# FLASH.net
KiCad netlist of a schematic drawn in Altium Designer
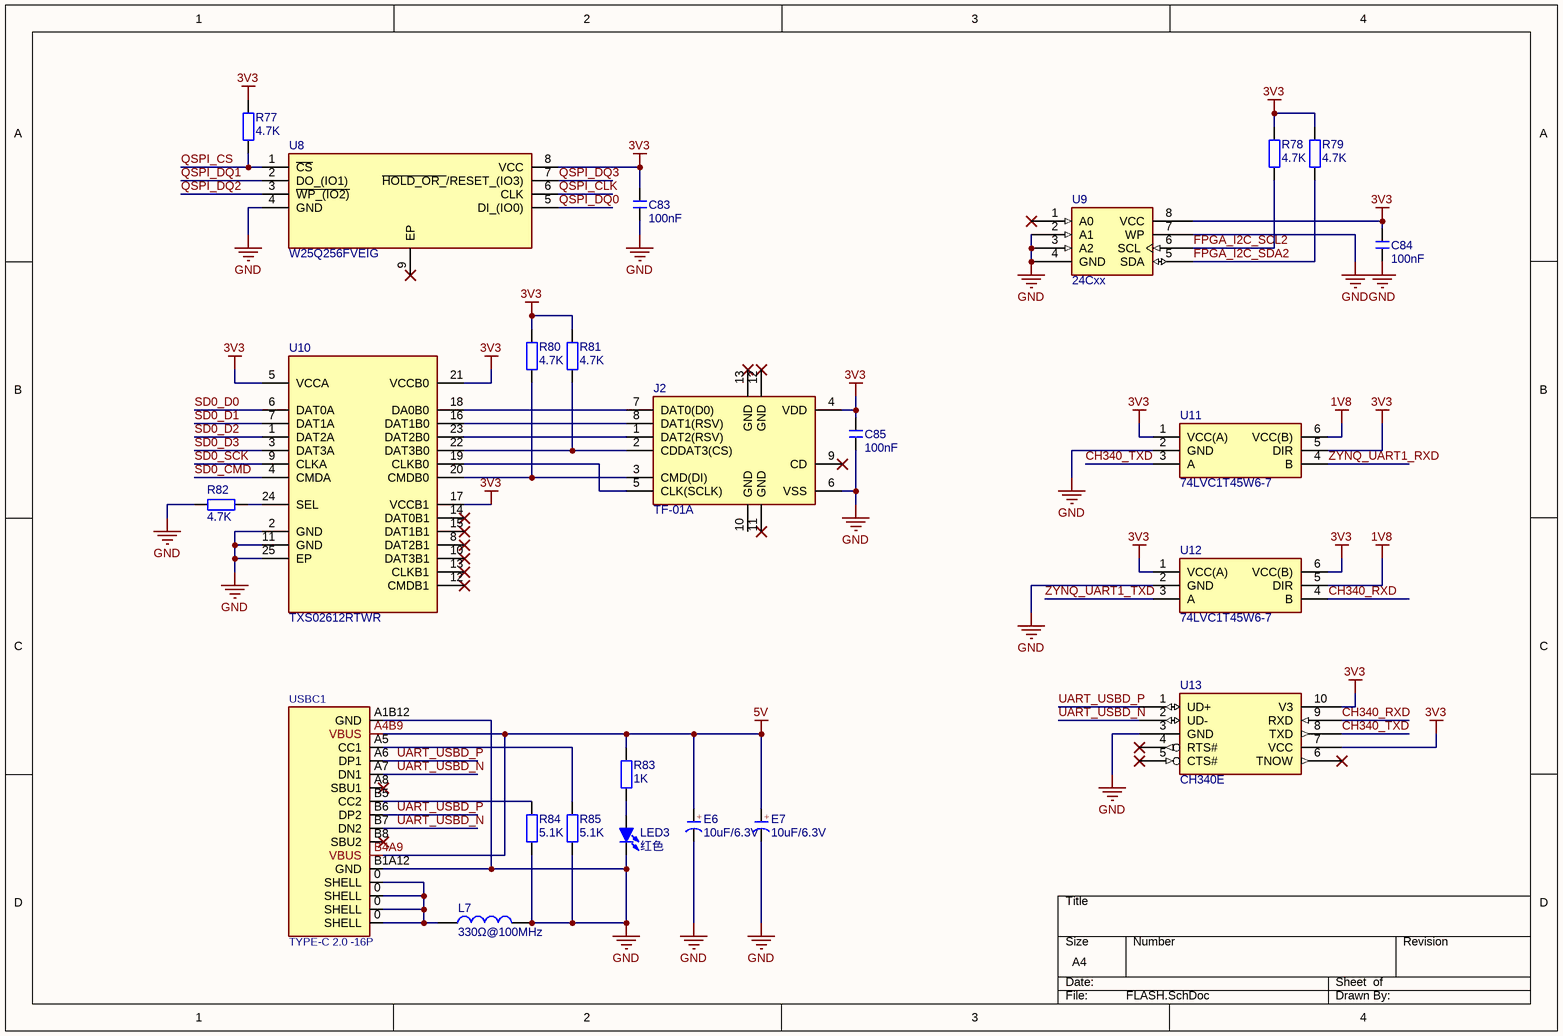
[diagram p0: FLASH.SchDoc]

(export (version "E")
  (design (tool "Eeschema 10.0.6"))
  (components
    (comp (ref "C83")
      (value "100nF")
      (footprint "C 0402_L")
      (description "无极性贴片电容")
      (fields (field (name "版权归属") "源创客"))
      (libsource (lib "3.1   - 电阻-电容-电感") (part "C"))
    )
    (comp (ref "C84")
      (value "100nF")
      (footprint "C 0402_L")
      (description "无极性贴片电容")
      (fields (field (name "版权归属") "源创客"))
      (libsource (lib "3.1   - 电阻-电容-电感") (part "C"))
    )
    (comp (ref "C85")
      (value "100nF")
      (footprint "C 0402_L")
      (description "无极性贴片电容")
      (fields (field (name "版权归属") "源创客"))
      (libsource (lib "3.1   - 电阻-电容-电感") (part "C"))
    )
    (comp (ref "E6")
      (value "10uF/6.3V")
      (footprint "CD A(3216)")
      (description "贴片钽电容")
      (fields (field (name "版权归属") "源创客"))
      (libsource (lib "3.1   - 电阻-电容-电感") (part "C-CD"))
    )
    (comp (ref "E7")
      (value "10uF/6.3V")
      (footprint "CD A(3216)")
      (description "贴片钽电容")
      (fields (field (name "版权归属") "源创客"))
      (libsource (lib "3.1   - 电阻-电容-电感") (part "C-CD"))
    )
    (comp (ref "J2")
      (value "TF-01A")
      (footprint "TF01A")
      (description "TF卡座")
      (libsource (lib "4.1   - 接口类") (part "TF-01A"))
    )
    (comp (ref "L7")
      (value "330Ω@100MHz")
      (footprint "L 0805")
      (description "小功率贴片电感")
      (fields (field (name "版权归属") "源创客"))
      (libsource (lib "3.1   - 电阻-电容-电感") (part "L"))
    )
    (comp (ref "LED3")
      (value "红色")
      (footprint "LED 0805G")
      (description "贴片LED")
      (fields (field (name "版权归属") "源创客"))
      (libsource (lib "9.1   - LED") (part "LED-SMD"))
    )
    (comp (ref "R77")
      (value "4.7K")
      (footprint "R 0402_L")
      (description "贴片电阻")
      (fields (field (name "版权归属") "源创客"))
      (libsource (lib "3.1   - 电阻-电容-电感") (part "R"))
    )
    (comp (ref "R78")
      (value "4.7K")
      (footprint "R 0402_L")
      (description "贴片电阻")
      (fields (field (name "版权归属") "源创客"))
      (libsource (lib "3.1   - 电阻-电容-电感") (part "R"))
    )
    (comp (ref "R79")
      (value "4.7K")
      (footprint "R 0402_L")
      (description "贴片电阻")
      (fields (field (name "版权归属") "源创客"))
      (libsource (lib "3.1   - 电阻-电容-电感") (part "R"))
    )
    (comp (ref "R80")
      (value "4.7K")
      (footprint "R 0402_L")
      (description "贴片电阻")
      (fields (field (name "版权归属") "源创客"))
      (libsource (lib "3.1   - 电阻-电容-电感") (part "R"))
    )
    (comp (ref "R81")
      (value "4.7K")
      (footprint "R 0402_L")
      (description "贴片电阻")
      (fields (field (name "版权归属") "源创客"))
      (libsource (lib "3.1   - 电阻-电容-电感") (part "R"))
    )
    (comp (ref "R82")
      (value "4.7K")
      (footprint "R 0402_L")
      (description "贴片电阻")
      (fields (field (name "版权归属") "源创客"))
      (libsource (lib "3.1   - 电阻-电容-电感") (part "R"))
    )
    (comp (ref "R83")
      (value "1K")
      (footprint "R 0402_L")
      (description "贴片电阻")
      (fields (field (name "版权归属") "源创客"))
      (libsource (lib "3.1   - 电阻-电容-电感") (part "R"))
    )
    (comp (ref "R84")
      (value "5.1K")
      (footprint "R 0402_L")
      (description "贴片电阻")
      (fields (field (name "版权归属") "源创客"))
      (libsource (lib "3.1   - 电阻-电容-电感") (part "R"))
    )
    (comp (ref "R85")
      (value "5.1K")
      (footprint "R 0402_L")
      (description "贴片电阻")
      (fields (field (name "版权归属") "源创客"))
      (libsource (lib "3.1   - 电阻-电容-电感") (part "R"))
    )
    (comp (ref "U8")
      (value "W25Q256FVEIG")
      (footprint "SON127P800X600X80-9N-D")
      (description "外置Flash")
      (libsource (lib "1.1   - IC芯片") (part "W25Q256FVEIG"))
    )
    (comp (ref "U9")
      (value "24Cxx")
      (footprint "SOP8_L")
      (description "外置EEPROM")
      (fields (field (name "版权归属") "源创客"))
      (libsource (lib "1.1   - IC芯片") (part "24Cxx"))
    )
    (comp (ref "U10")
      (value "TXS02612RTWR")
      (footprint "QFN24 4x4_L")
      (description "SD/TF卡芯片")
      (fields (field (name "MOUSER PART NUMBER") "595-TXS02612RTWR"))
      (libsource (lib "1.1   - IC芯片") (part "TXS02612RTWR"))
    )
    (comp (ref "U11")
      (value "74LVC1T45W6-7")
      (footprint "SOT23-6L")
      (description "单向电平转换")
      (fields (field (name "MOUSER PART NUMBER") "621-74LVC1T45W6-7"))
      (libsource (lib "1.2   - 74系列芯片") (part "74LVC1T45W6-7"))
    )
    (comp (ref "U12")
      (value "74LVC1T45W6-7")
      (footprint "SOT23-6L")
      (description "单向电平转换")
      (fields (field (name "MOUSER PART NUMBER") "621-74LVC1T45W6-7"))
      (libsource (lib "1.2   - 74系列芯片") (part "74LVC1T45W6-7"))
    )
    (comp (ref "U13")
      (value "CH340E")
      (footprint "MSOP10_L")
      (description "USB转串口")
      (libsource (lib "1.1   - IC芯片") (part "CH340E"))
    )
    (comp (ref "USBC1")
      (value "TYPE-C 2.0 -16P")
      (footprint "USB-C-SMD_16P")
      (description "USB2.0_Type-C_16Pin母座")
      (libsource (lib "0.6 - 电源_RJ45以太网_音频_SD-TF_SIM_ USB Type-C_HDMI插座") (part "USB2.0_Type-C_16Pin"))
    )
  )
  (nets
    (net (code "1") (name "/CH340_RXD") (class "Default")
      (node (ref "U12") (pin "4") (pinfunction "B_4") (pintype "passive"))
      (node (ref "U13") (pin "9") (pinfunction "RXD_9") (pintype "input"))
    )
    (net (code "2") (name "/CH340_TXD") (class "Default")
      (node (ref "U11") (pin "3") (pinfunction "A_3") (pintype "passive"))
      (node (ref "U13") (pin "8") (pinfunction "TXD_8") (pintype "output"))
    )
    (net (code "3") (name "/FPGA_I2C_SCL2") (class "Default")
      (node (ref "R78") (pin "2") (pinfunction "2_2") (pintype "passive"))
      (node (ref "U9") (pin "6") (pinfunction "SCL_6") (pintype "input"))
    )
    (net (code "4") (name "/FPGA_I2C_SDA2") (class "Default")
      (node (ref "R79") (pin "2") (pinfunction "2_2") (pintype "passive"))
      (node (ref "U9") (pin "5") (pinfunction "SDA_5") (pintype "bidirectional"))
    )
    (net (code "5") (name "/QSPI_CLK") (class "Default")
      (node (ref "U8") (pin "6") (pinfunction "CLK_6") (pintype "passive"))
    )
    (net (code "6") (name "/QSPI_CS") (class "Default")
      (node (ref "R77") (pin "2") (pinfunction "2_2") (pintype "passive"))
      (node (ref "U8") (pin "1") (pinfunction "~{CS}_1") (pintype "passive"))
    )
    (net (code "7") (name "/QSPI_DQ0") (class "Default")
      (node (ref "U8") (pin "5") (pinfunction "DI_(IO0)_5") (pintype "passive"))
    )
    (net (code "8") (name "/QSPI_DQ1") (class "Default")
      (node (ref "U8") (pin "2") (pinfunction "DO_(IO1)_2") (pintype "passive"))
    )
    (net (code "9") (name "/QSPI_DQ2") (class "Default")
      (node (ref "U8") (pin "3") (pinfunction "~{WP_(IO2)}_3") (pintype "passive"))
    )
    (net (code "10") (name "/QSPI_DQ3") (class "Default")
      (node (ref "U8") (pin "7") (pinfunction "~{HOLD_OR_}/RESET_(IO3)_7") (pintype "passive"))
    )
    (net (code "11") (name "/SD0_CMD") (class "Default")
      (node (ref "U10") (pin "4") (pinfunction "CMDA_4") (pintype "passive"))
    )
    (net (code "12") (name "/SD0_D0") (class "Default")
      (node (ref "U10") (pin "6") (pinfunction "DAT0A_6") (pintype "passive"))
    )
    (net (code "13") (name "/SD0_D1") (class "Default")
      (node (ref "U10") (pin "7") (pinfunction "DAT1A_7") (pintype "passive"))
    )
    (net (code "14") (name "/SD0_D2") (class "Default")
      (node (ref "U10") (pin "1") (pinfunction "DAT2A_1") (pintype "passive"))
    )
    (net (code "15") (name "/SD0_D3") (class "Default")
      (node (ref "U10") (pin "3") (pinfunction "DAT3A_3") (pintype "passive"))
    )
    (net (code "16") (name "/SD0_SCK") (class "Default")
      (node (ref "U10") (pin "9") (pinfunction "CLKA_9") (pintype "passive"))
    )
    (net (code "17") (name "/UART_USBD_N") (class "Default")
      (node (ref "U13") (pin "2") (pinfunction "UD-_2") (pintype "bidirectional"))
      (node (ref "USBC1") (pin "A7") (pinfunction "DN1_A7") (pintype "passive"))
      (node (ref "USBC1") (pin "B7") (pinfunction "DN2_B7") (pintype "passive"))
    )
    (net (code "18") (name "/UART_USBD_P") (class "Default")
      (node (ref "U13") (pin "1") (pinfunction "UD+_1") (pintype "bidirectional"))
      (node (ref "USBC1") (pin "A6") (pinfunction "DP1_A6") (pintype "passive"))
      (node (ref "USBC1") (pin "B6") (pinfunction "DP2_B6") (pintype "passive"))
    )
    (net (code "19") (name "/ZYNQ_UART1_RXD") (class "Default")
      (node (ref "U11") (pin "4") (pinfunction "B_4") (pintype "passive"))
    )
    (net (code "20") (name "/ZYNQ_UART1_TXD") (class "Default")
      (node (ref "U12") (pin "3") (pinfunction "A_3") (pintype "passive"))
    )
    (net (code "21") (name "1V8") (class "Default")
      (node (ref "U11") (pin "6") (pinfunction "VCC(B)_6") (pintype "passive"))
      (node (ref "U12") (pin "5") (pinfunction "DIR_5") (pintype "passive"))
    )
    (net (code "22") (name "3V3") (class "Default")
      (node (ref "C83") (pin "2") (pinfunction "2_2") (pintype "passive"))
      (node (ref "C84") (pin "2") (pinfunction "2_2") (pintype "passive"))
      (node (ref "C85") (pin "2") (pinfunction "2_2") (pintype "passive"))
      (node (ref "J2") (pin "4") (pinfunction "VDD_4") (pintype "passive"))
      (node (ref "R77") (pin "1") (pinfunction "1_1") (pintype "passive"))
      (node (ref "R78") (pin "1") (pinfunction "1_1") (pintype "passive"))
      (node (ref "R79") (pin "1") (pinfunction "1_1") (pintype "passive"))
      (node (ref "R80") (pin "1") (pinfunction "1_1") (pintype "passive"))
      (node (ref "R81") (pin "1") (pinfunction "1_1") (pintype "passive"))
      (node (ref "U10") (pin "17") (pinfunction "VCCB1_17") (pintype "passive"))
      (node (ref "U10") (pin "21") (pinfunction "VCCB0_21") (pintype "passive"))
      (node (ref "U10") (pin "5") (pinfunction "VCCA_5") (pintype "passive"))
      (node (ref "U11") (pin "1") (pinfunction "VCC(A)_1") (pintype "passive"))
      (node (ref "U11") (pin "5") (pinfunction "DIR_5") (pintype "passive"))
      (node (ref "U12") (pin "1") (pinfunction "VCC(A)_1") (pintype "passive"))
      (node (ref "U12") (pin "6") (pinfunction "VCC(B)_6") (pintype "passive"))
      (node (ref "U13") (pin "10") (pinfunction "V3_10") (pintype "power_in"))
      (node (ref "U13") (pin "7") (pinfunction "VCC_7") (pintype "power_in"))
      (node (ref "U8") (pin "8") (pinfunction "VCC_8") (pintype "passive"))
      (node (ref "U9") (pin "8") (pinfunction "VCC_8") (pintype "power_in"))
    )
    (net (code "23") (name "5V") (class "Default")
      (node (ref "E6") (pin "1") (pinfunction "A_1") (pintype "passive"))
      (node (ref "E7") (pin "1") (pinfunction "A_1") (pintype "passive"))
      (node (ref "R83") (pin "2") (pinfunction "2_2") (pintype "passive"))
      (node (ref "USBC1") (pin "A4B9") (pinfunction "VBUS_A4B9") (pintype "passive"))
      (node (ref "USBC1") (pin "B4A9") (pinfunction "VBUS_B4A9") (pintype "passive"))
    )
    (net (code "24") (name "GND") (class "Default")
      (node (ref "C83") (pin "1") (pinfunction "1_1") (pintype "passive"))
      (node (ref "C84") (pin "1") (pinfunction "1_1") (pintype "passive"))
      (node (ref "C85") (pin "1") (pinfunction "1_1") (pintype "passive"))
      (node (ref "E6") (pin "2") (pinfunction "K_2") (pintype "passive"))
      (node (ref "E7") (pin "2") (pinfunction "K_2") (pintype "passive"))
      (node (ref "J2") (pin "6") (pinfunction "VSS_6") (pintype "passive"))
      (node (ref "L7") (pin "2") (pinfunction "2_2") (pintype "passive"))
      (node (ref "LED3") (pin "2") (pinfunction "K_2") (pintype "passive"))
      (node (ref "R82") (pin "1") (pinfunction "1_1") (pintype "passive"))
      (node (ref "R84") (pin "1") (pinfunction "1_1") (pintype "passive"))
      (node (ref "R85") (pin "1") (pinfunction "1_1") (pintype "passive"))
      (node (ref "U10") (pin "11") (pinfunction "GND_11") (pintype "passive"))
      (node (ref "U10") (pin "2") (pinfunction "GND_2") (pintype "passive"))
      (node (ref "U10") (pin "25") (pinfunction "EP_25") (pintype "passive"))
      (node (ref "U11") (pin "2") (pinfunction "GND_2") (pintype "passive"))
      (node (ref "U12") (pin "2") (pinfunction "GND_2") (pintype "passive"))
      (node (ref "U13") (pin "3") (pinfunction "GND_3") (pintype "power_in"))
      (node (ref "U8") (pin "4") (pinfunction "GND_4") (pintype "passive"))
      (node (ref "U9") (pin "2") (pinfunction "A1_2") (pintype "input"))
      (node (ref "U9") (pin "3") (pinfunction "A2_3") (pintype "input"))
      (node (ref "U9") (pin "4") (pinfunction "GND_4") (pintype "passive"))
      (node (ref "U9") (pin "7") (pinfunction "WP_7") (pintype "passive"))
      (node (ref "USBC1") (pin "A1B12") (pinfunction "GND_A1B12") (pintype "passive"))
      (node (ref "USBC1") (pin "B1A12") (pinfunction "GND_B1A12") (pintype "passive"))
    )
    (net (code "25") (name "Net-(J2-CDDAT3(CS))") (class "Default")
      (node (ref "J2") (pin "2") (pinfunction "CDDAT3(CS)_2") (pintype "passive"))
      (node (ref "R81") (pin "2") (pinfunction "2_2") (pintype "passive"))
      (node (ref "U10") (pin "22") (pinfunction "DAT3B0_22") (pintype "passive"))
    )
    (net (code "26") (name "Net-(J2-CLK(SCLK))") (class "Default")
      (node (ref "J2") (pin "5") (pinfunction "CLK(SCLK)_5") (pintype "passive"))
      (node (ref "U10") (pin "19") (pinfunction "CLKB0_19") (pintype "passive"))
    )
    (net (code "27") (name "Net-(J2-CMD(DI))") (class "Default")
      (node (ref "J2") (pin "3") (pinfunction "CMD(DI)_3") (pintype "passive"))
      (node (ref "R80") (pin "2") (pinfunction "2_2") (pintype "passive"))
      (node (ref "U10") (pin "20") (pinfunction "CMDB0_20") (pintype "passive"))
    )
    (net (code "28") (name "Net-(J2-DAT0(D0))") (class "Default")
      (node (ref "J2") (pin "7") (pinfunction "DAT0(D0)_7") (pintype "passive"))
      (node (ref "U10") (pin "18") (pinfunction "DA0B0_18") (pintype "passive"))
    )
    (net (code "29") (name "Net-(J2-DAT1(RSV))") (class "Default")
      (node (ref "J2") (pin "8") (pinfunction "DAT1(RSV)_8") (pintype "passive"))
      (node (ref "U10") (pin "16") (pinfunction "DAT1B0_16") (pintype "passive"))
    )
    (net (code "30") (name "Net-(J2-DAT2(RSV))") (class "Default")
      (node (ref "J2") (pin "1") (pinfunction "DAT2(RSV)_1") (pintype "passive"))
      (node (ref "U10") (pin "23") (pinfunction "DAT2B0_23") (pintype "passive"))
    )
    (net (code "31") (name "Net-(LED3-A)") (class "Default")
      (node (ref "LED3") (pin "1") (pinfunction "A_1") (pintype "passive"))
      (node (ref "R83") (pin "1") (pinfunction "1_1") (pintype "passive"))
    )
    (net (code "32") (name "Net-(U10-SEL)") (class "Default")
      (node (ref "R82") (pin "2") (pinfunction "2_2") (pintype "passive"))
      (node (ref "U10") (pin "24") (pinfunction "SEL_24") (pintype "passive"))
    )
    (net (code "33") (name "Net-(USBC1-CC1)") (class "Default")
      (node (ref "R85") (pin "2") (pinfunction "2_2") (pintype "passive"))
      (node (ref "USBC1") (pin "A5") (pinfunction "CC1_A5") (pintype "passive"))
    )
    (net (code "34") (name "Net-(USBC1-CC2)") (class "Default")
      (node (ref "R84") (pin "2") (pinfunction "2_2") (pintype "passive"))
      (node (ref "USBC1") (pin "B5") (pinfunction "CC2_B5") (pintype "passive"))
    )
    (net (code "35") (name "Net-(USBC1-SHELL)") (class "Default")
      (node (ref "L7") (pin "1") (pinfunction "1_1") (pintype "passive"))
      (node (ref "USBC1") (pin "0") (pinfunction "SHELL_0") (pintype "passive"))
    )
    (net (code "36") (name "unconnected-(J2-CD-Pad9)") (class "Default")
      (node (ref "J2") (pin "9") (pinfunction "CD_9") (pintype "passive+no_connect"))
    )
    (net (code "37") (name "unconnected-(J2-GND-Pad10)") (class "Default")
      (node (ref "J2") (pin "10") (pinfunction "GND_10") (pintype "passive"))
    )
    (net (code "38") (name "unconnected-(J2-GND-Pad11)") (class "Default")
      (node (ref "J2") (pin "11") (pinfunction "GND_11") (pintype "passive+no_connect"))
    )
    (net (code "39") (name "unconnected-(J2-GND-Pad12)") (class "Default")
      (node (ref "J2") (pin "12") (pinfunction "GND_12") (pintype "passive+no_connect"))
    )
    (net (code "40") (name "unconnected-(J2-GND-Pad13)") (class "Default")
      (node (ref "J2") (pin "13") (pinfunction "GND_13") (pintype "passive+no_connect"))
    )
    (net (code "41") (name "unconnected-(U8-EP-Pad9)") (class "Default")
      (node (ref "U8") (pin "9") (pinfunction "EP_9") (pintype "passive+no_connect"))
    )
    (net (code "42") (name "unconnected-(U9-A0-Pad1)") (class "Default")
      (node (ref "U9") (pin "1") (pinfunction "A0_1") (pintype "input+no_connect"))
    )
    (net (code "43") (name "unconnected-(U10-CLKB1-Pad13)") (class "Default")
      (node (ref "U10") (pin "13") (pinfunction "CLKB1_13") (pintype "passive+no_connect"))
    )
    (net (code "44") (name "unconnected-(U10-CMDB1-Pad12)") (class "Default")
      (node (ref "U10") (pin "12") (pinfunction "CMDB1_12") (pintype "passive+no_connect"))
    )
    (net (code "45") (name "unconnected-(U10-DAT0B1-Pad14)") (class "Default")
      (node (ref "U10") (pin "14") (pinfunction "DAT0B1_14") (pintype "passive+no_connect"))
    )
    (net (code "46") (name "unconnected-(U10-DAT1B1-Pad15)") (class "Default")
      (node (ref "U10") (pin "15") (pinfunction "DAT1B1_15") (pintype "passive+no_connect"))
    )
    (net (code "47") (name "unconnected-(U10-DAT2B1-Pad8)") (class "Default")
      (node (ref "U10") (pin "8") (pinfunction "DAT2B1_8") (pintype "passive+no_connect"))
    )
    (net (code "48") (name "unconnected-(U10-DAT3B1-Pad10)") (class "Default")
      (node (ref "U10") (pin "10") (pinfunction "DAT3B1_10") (pintype "passive+no_connect"))
    )
    (net (code "49") (name "unconnected-(U13-CTS#-Pad5)") (class "Default")
      (node (ref "U13") (pin "5") (pinfunction "CTS#_5") (pintype "input+no_connect"))
    )
    (net (code "50") (name "unconnected-(U13-RTS#-Pad4)") (class "Default")
      (node (ref "U13") (pin "4") (pinfunction "RTS#_4") (pintype "output+no_connect"))
    )
    (net (code "51") (name "unconnected-(U13-TNOW-Pad6)") (class "Default")
      (node (ref "U13") (pin "6") (pinfunction "TNOW_6") (pintype "output+no_connect"))
    )
    (net (code "52") (name "unconnected-(USBC1-SBU1-PadA8)") (class "Default")
      (node (ref "USBC1") (pin "A8") (pinfunction "SBU1_A8") (pintype "passive+no_connect"))
    )
    (net (code "53") (name "unconnected-(USBC1-SBU2-PadB8)") (class "Default")
      (node (ref "USBC1") (pin "B8") (pinfunction "SBU2_B8") (pintype "passive+no_connect"))
    )
  )
)
